# MySensors_AirQuality_Board_2017-11-26_i2.net
KiCad netlist of a schematic drawn in EAGLE
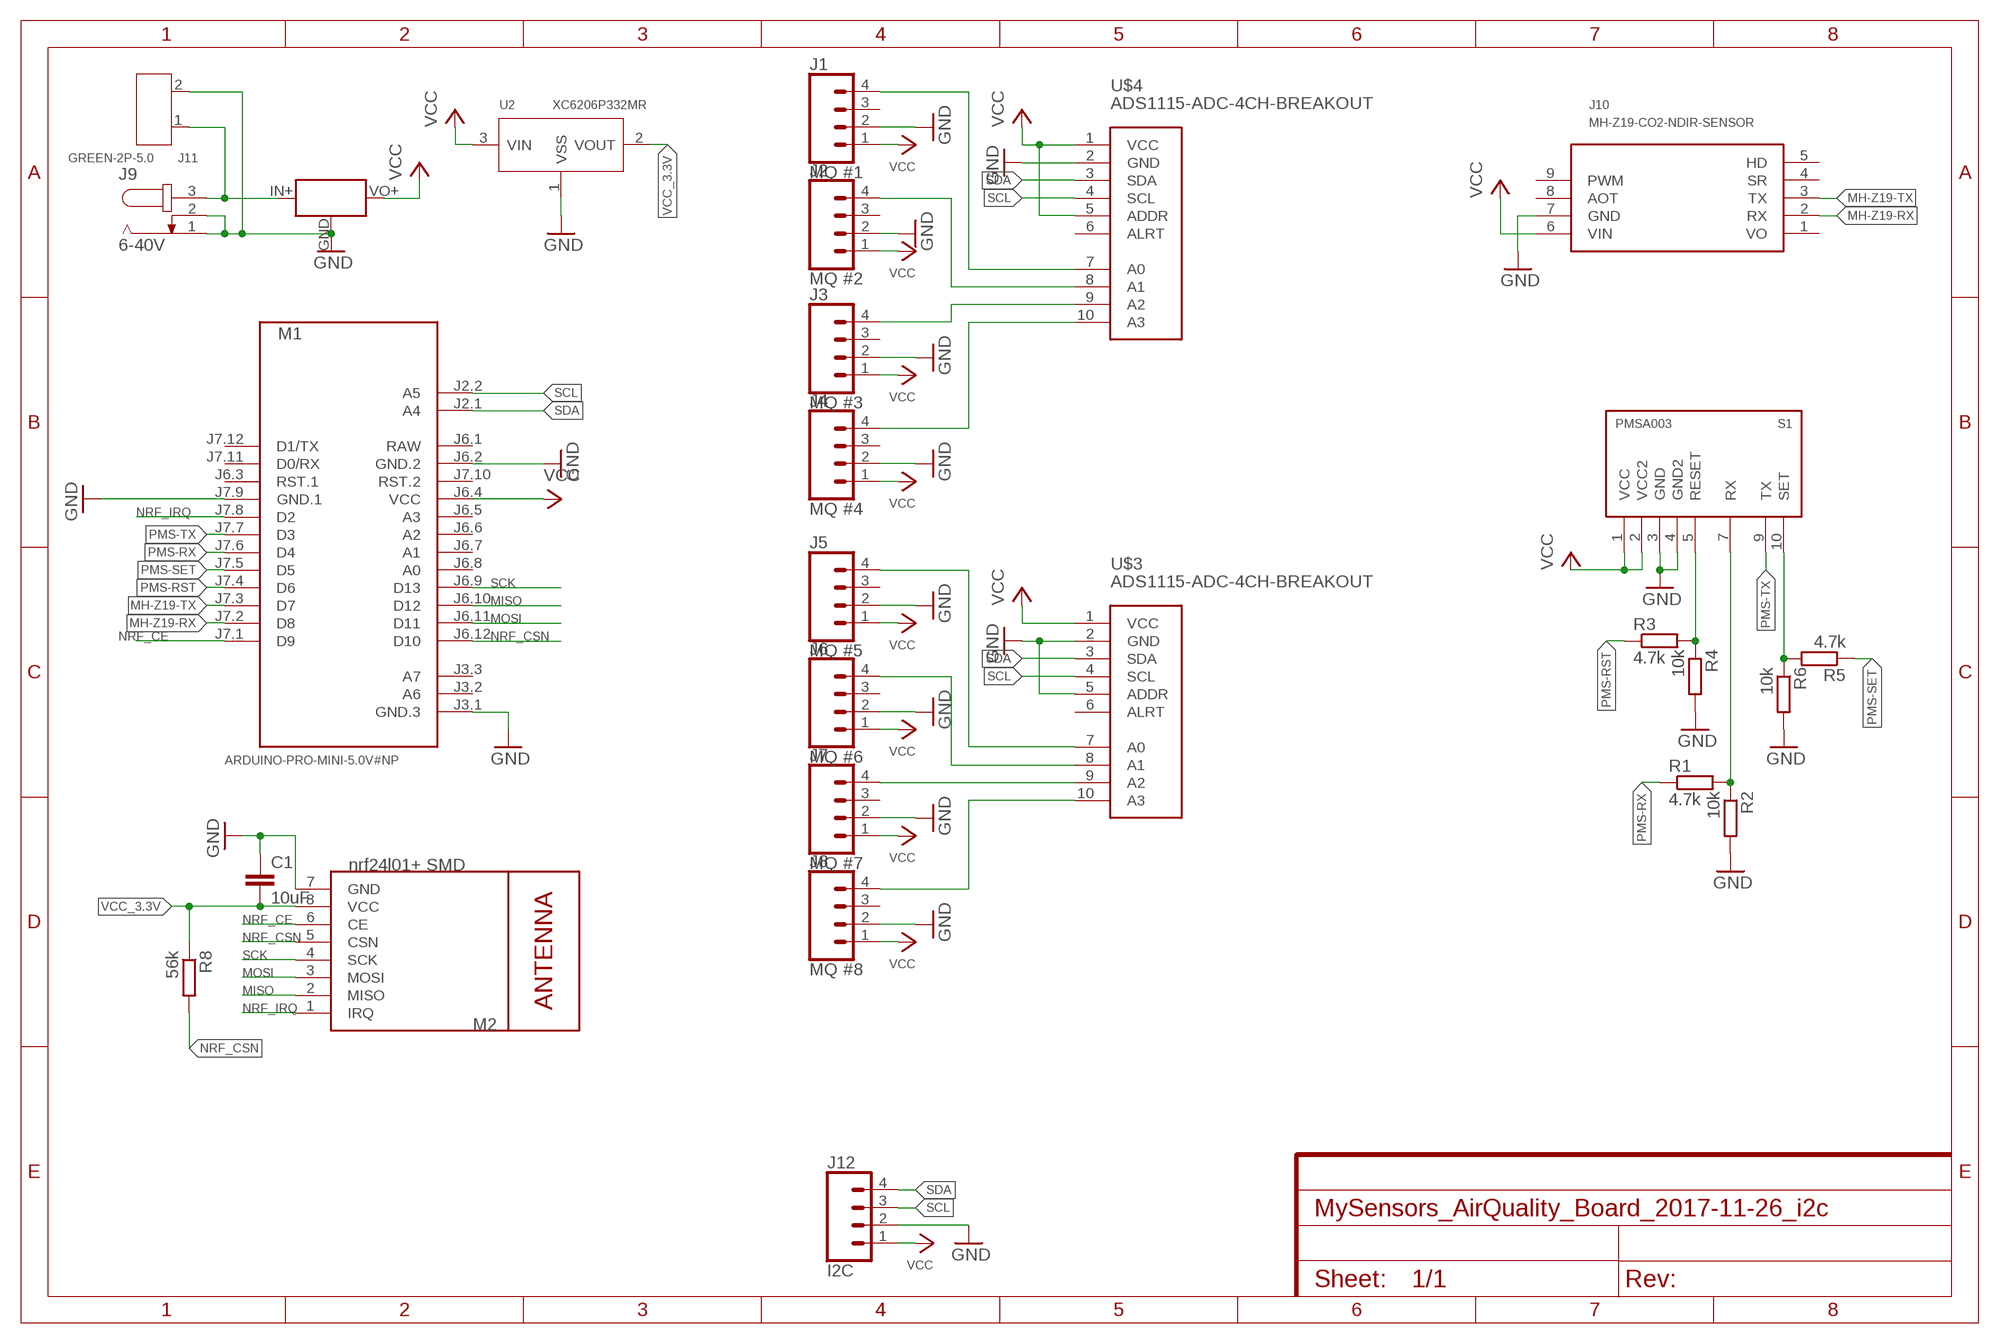
[diagram p0: schematic, sheet 1]

(export (version "E")
  (design (tool "Eeschema 10.0.6"))
  (components
    (comp (ref "C1")
      (value "10uF")
      (footprint "eagle-import:C0805")
      (libsource (lib "eagle-import") (part "C-EUC0805"))
    )
    (comp (ref "J1")
      (value "MQ #1")
      (footprint "eagle-import:1X04")
      (libsource (lib "eagle-import") (part "CONN_04"))
    )
    (comp (ref "J2")
      (value "MQ #2")
      (footprint "eagle-import:1X04")
      (libsource (lib "eagle-import") (part "CONN_04"))
    )
    (comp (ref "J3")
      (value "MQ #3")
      (footprint "eagle-import:1X04")
      (libsource (lib "eagle-import") (part "CONN_04"))
    )
    (comp (ref "J4")
      (value "MQ #4")
      (footprint "eagle-import:1X04")
      (libsource (lib "eagle-import") (part "CONN_04"))
    )
    (comp (ref "J5")
      (value "MQ #5")
      (footprint "eagle-import:1X04")
      (libsource (lib "eagle-import") (part "CONN_04"))
    )
    (comp (ref "J6")
      (value "MQ #6")
      (footprint "eagle-import:1X04")
      (libsource (lib "eagle-import") (part "CONN_04"))
    )
    (comp (ref "J7")
      (value "MQ #7")
      (footprint "eagle-import:1X04")
      (libsource (lib "eagle-import") (part "CONN_04"))
    )
    (comp (ref "J8")
      (value "MQ #8")
      (footprint "eagle-import:1X04")
      (libsource (lib "eagle-import") (part "CONN_04"))
    )
    (comp (ref "J9")
      (value "6-40V")
      (footprint "eagle-import:SPC4078")
      (libsource (lib "eagle-import") (part "JACK-PLUG1"))
    )
    (comp (ref "J10")
      (value "MH-Z19-CO2-NDIR-SENSOR")
      (footprint "eagle-import:MH-Z19")
      (libsource (lib "eagle-import") (part "MH-Z19-CO2-NDIR-SENSOR"))
    )
    (comp (ref "J11")
      (value "GREEN-2P-5.0")
      (footprint "eagle-import:H2-5.0-10.5X8.0MM")
      (libsource (lib "eagle-import") (part "SCREW-TERMINAL-GREEN(2P-5.0)"))
    )
    (comp (ref "J12")
      (value "I2C")
      (footprint "eagle-import:1X04")
      (libsource (lib "eagle-import") (part "CONN_04"))
    )
    (comp (ref "M1")
      (value "ARDUINO-PRO-MINI-5.0V#NP")
      (footprint "eagle-import:ARDUINO-PRO-MINI#NP")
      (libsource (lib "eagle-import") (part "ARDUINO-PRO-MINI-#NP5.0V"))
    )
    (comp (ref "M2")
      (value "nrf24l01+ SMD")
      (footprint "eagle-import:WIRELESS-NRF24L01-SMD")
      (libsource (lib "eagle-import") (part "WIRELESS-NRF24L01SMD"))
    )
    (comp (ref "R1")
      (value "4.7k")
      (footprint "eagle-import:R0805")
      (libsource (lib "eagle-import") (part "resistor_348_R-EU_R0805"))
    )
    (comp (ref "R2")
      (value "10k")
      (footprint "eagle-import:R0805")
      (libsource (lib "eagle-import") (part "resistor_348_R-EU_R0805"))
    )
    (comp (ref "R3")
      (value "4.7k")
      (footprint "eagle-import:R0805")
      (libsource (lib "eagle-import") (part "resistor_348_R-EU_R0805"))
    )
    (comp (ref "R4")
      (value "10k")
      (footprint "eagle-import:R0805")
      (libsource (lib "eagle-import") (part "resistor_348_R-EU_R0805"))
    )
    (comp (ref "R5")
      (value "4.7k")
      (footprint "eagle-import:R0805")
      (libsource (lib "eagle-import") (part "resistor_348_R-EU_R0805"))
    )
    (comp (ref "R6")
      (value "10k")
      (footprint "eagle-import:R0805")
      (libsource (lib "eagle-import") (part "resistor_348_R-EU_R0805"))
    )
    (comp (ref "R8")
      (value "56k")
      (footprint "eagle-import:R0805")
      (libsource (lib "eagle-import") (part "R-EU_R0805"))
    )
    (comp (ref "S1")
      (value "PMSA003")
      (footprint "eagle-import:PMSA003")
      (libsource (lib "eagle-import") (part "PMSA003"))
    )
    (comp (ref "U$2")
      (value "MINI_BUCK_CONVERTER")
      (footprint "eagle-import:MINI_BUCK_CONVERTER")
      (libsource (lib "eagle-import") (part "MINI_BUCK_CONVERTER"))
    )
    (comp (ref "U$3")
      (value "ADS1115-ADC-4CH-BREAKOUT")
      (footprint "eagle-import:ADS1115-ADC-4CH-BREAKOUT")
      (libsource (lib "eagle-import") (part "ADS1115-ADC-4CH-BREAKOUT"))
    )
    (comp (ref "U$4")
      (value "ADS1115-ADC-4CH-BREAKOUT")
      (footprint "eagle-import:ADS1115-ADC-4CH-BREAKOUT")
      (libsource (lib "eagle-import") (part "ADS1115-ADC-4CH-BREAKOUT"))
    )
    (comp (ref "U2")
      (value "XC6206P332MR")
      (footprint "eagle-import:SOT-23")
      (fields (field (name "MPN") "XC6206P332MR-G"))
      (libsource (lib "eagle-import") (part "PMIC-LDO-XC6206P332MR-G(SOT23)"))
    )
  )
  (nets
    (net (code "1") (name "/MISO") (class "Default")
      (node (ref "M1") (pin "J6.10") (pinfunction "D12_J6.10") (pintype "bidirectional"))
      (node (ref "M2") (pin "2") (pinfunction "MISO_2") (pintype "bidirectional"))
    )
    (net (code "2") (name "/MOSI") (class "Default")
      (node (ref "M1") (pin "J6.11") (pinfunction "D11_J6.11") (pintype "bidirectional"))
      (node (ref "M2") (pin "3") (pinfunction "MOSI_3") (pintype "bidirectional"))
    )
    (net (code "3") (name "/NRF_CE") (class "Default")
      (node (ref "M1") (pin "J7.1") (pinfunction "D9_J7.1") (pintype "bidirectional"))
      (node (ref "M2") (pin "6") (pinfunction "CE_6") (pintype "bidirectional"))
    )
    (net (code "4") (name "/NRF_IRQ") (class "Default")
      (node (ref "M1") (pin "J7.8") (pinfunction "D2_J7.8") (pintype "bidirectional"))
      (node (ref "M2") (pin "1") (pinfunction "IRQ_1") (pintype "bidirectional"))
    )
    (net (code "5") (name "/RAW") (class "Default")
      (node (ref "M1") (pin "J6.1") (pinfunction "RAW_J6.1") (pintype "power_in"))
    )
    (net (code "6") (name "/SCK") (class "Default")
      (node (ref "M1") (pin "J6.9") (pinfunction "D13_J6.9") (pintype "bidirectional"))
      (node (ref "M2") (pin "4") (pinfunction "SCK_4") (pintype "bidirectional"))
    )
    (net (code "7") (name "/VO") (class "Default")
      (node (ref "J10") (pin "1") (pinfunction "VO_1") (pintype "power_in"))
    )
    (net (code "8") (name "GND") (class "Default")
      (node (ref "C1") (pin "1") (pinfunction "1_1") (pintype "passive"))
      (node (ref "J1") (pin "2") (pinfunction "2_2") (pintype "passive"))
      (node (ref "J10") (pin "7") (pinfunction "GND_7") (pintype "power_in"))
      (node (ref "J11") (pin "2") (pinfunction "2_2") (pintype "bidirectional"))
      (node (ref "J12") (pin "2") (pinfunction "2_2") (pintype "passive"))
      (node (ref "J2") (pin "2") (pinfunction "2_2") (pintype "passive"))
      (node (ref "J3") (pin "2") (pinfunction "2_2") (pintype "passive"))
      (node (ref "J4") (pin "2") (pinfunction "2_2") (pintype "passive"))
      (node (ref "J5") (pin "2") (pinfunction "2_2") (pintype "passive"))
      (node (ref "J6") (pin "2") (pinfunction "2_2") (pintype "passive"))
      (node (ref "J7") (pin "2") (pinfunction "2_2") (pintype "passive"))
      (node (ref "J8") (pin "2") (pinfunction "2_2") (pintype "passive"))
      (node (ref "J9") (pin "1") (pinfunction "1_1") (pintype "passive"))
      (node (ref "J9") (pin "2") (pinfunction "2_2") (pintype "passive"))
      (node (ref "M1") (pin "J3.1") (pinfunction "GND.3_J3.1") (pintype "bidirectional"))
      (node (ref "M1") (pin "J6.2") (pinfunction "GND.2_J6.2") (pintype "power_in"))
      (node (ref "M1") (pin "J7.9") (pinfunction "GND.1_J7.9") (pintype "power_in"))
      (node (ref "M2") (pin "7") (pinfunction "GND_7") (pintype "power_in"))
      (node (ref "R2") (pin "2") (pinfunction "2_2") (pintype "passive"))
      (node (ref "R4") (pin "2") (pinfunction "2_2") (pintype "passive"))
      (node (ref "R6") (pin "2") (pinfunction "2_2") (pintype "passive"))
      (node (ref "S1") (pin "3") (pinfunction "GND_3") (pintype "bidirectional"))
      (node (ref "S1") (pin "4") (pinfunction "GND2_4") (pintype "bidirectional"))
      (node (ref "U$2") (pin "GND") (pinfunction "GND_GND") (pintype "bidirectional"))
      (node (ref "U$3") (pin "2") (pinfunction "GND_2") (pintype "power_in"))
      (node (ref "U$3") (pin "5") (pinfunction "ADDR_5") (pintype "bidirectional"))
      (node (ref "U$4") (pin "2") (pinfunction "GND_2") (pintype "power_in"))
      (node (ref "U2") (pin "1") (pinfunction "VSS_1") (pintype "power_in"))
    )
    (net (code "9") (name "MH-Z19-RX") (class "Default")
      (node (ref "J10") (pin "2") (pinfunction "RX_2") (pintype "input"))
      (node (ref "M1") (pin "J7.2") (pinfunction "D8_J7.2") (pintype "bidirectional"))
    )
    (net (code "10") (name "MH-Z19-TX") (class "Default")
      (node (ref "J10") (pin "3") (pinfunction "TX_3") (pintype "output"))
      (node (ref "M1") (pin "J7.3") (pinfunction "D7_J7.3") (pintype "bidirectional"))
    )
    (net (code "11") (name "NRF_CSN") (class "Default")
      (node (ref "M1") (pin "J6.12") (pinfunction "D10_J6.12") (pintype "bidirectional"))
      (node (ref "M2") (pin "5") (pinfunction "CSN_5") (pintype "bidirectional"))
      (node (ref "R8") (pin "2") (pinfunction "2_2") (pintype "passive"))
    )
    (net (code "12") (name "Net-(S1-RESET)") (class "Default")
      (node (ref "R3") (pin "2") (pinfunction "2_2") (pintype "passive"))
      (node (ref "R4") (pin "1") (pinfunction "1_1") (pintype "passive"))
      (node (ref "S1") (pin "5") (pinfunction "RESET_5") (pintype "bidirectional"))
    )
    (net (code "13") (name "Net-(S1-RX)") (class "Default")
      (node (ref "R1") (pin "2") (pinfunction "2_2") (pintype "passive"))
      (node (ref "R2") (pin "1") (pinfunction "1_1") (pintype "passive"))
      (node (ref "S1") (pin "7") (pinfunction "RX_7") (pintype "bidirectional"))
    )
    (net (code "14") (name "Net-(S1-SET)") (class "Default")
      (node (ref "R5") (pin "2") (pinfunction "2_2") (pintype "passive"))
      (node (ref "R6") (pin "1") (pinfunction "1_1") (pintype "passive"))
      (node (ref "S1") (pin "10") (pinfunction "SET_10") (pintype "bidirectional"))
    )
    (net (code "15") (name "Net-(U$2-VIN)") (class "Default")
      (node (ref "J11") (pin "1") (pinfunction "1_1") (pintype "bidirectional"))
      (node (ref "J9") (pin "3") (pinfunction "3_3") (pintype "passive"))
      (node (ref "U$2") (pin "IN+") (pinfunction "VIN_IN+") (pintype "input"))
    )
    (net (code "16") (name "Net-(U$3-A0)") (class "Default")
      (node (ref "J5") (pin "4") (pinfunction "4_4") (pintype "passive"))
      (node (ref "U$3") (pin "7") (pinfunction "A0_7") (pintype "input"))
    )
    (net (code "17") (name "Net-(U$3-A1)") (class "Default")
      (node (ref "J6") (pin "4") (pinfunction "4_4") (pintype "passive"))
      (node (ref "U$3") (pin "8") (pinfunction "A1_8") (pintype "input"))
    )
    (net (code "18") (name "Net-(U$3-A2)") (class "Default")
      (node (ref "J7") (pin "4") (pinfunction "4_4") (pintype "passive"))
      (node (ref "U$3") (pin "9") (pinfunction "A2_9") (pintype "input"))
    )
    (net (code "19") (name "Net-(U$3-A3)") (class "Default")
      (node (ref "J8") (pin "4") (pinfunction "4_4") (pintype "passive"))
      (node (ref "U$3") (pin "10") (pinfunction "A3_10") (pintype "input"))
    )
    (net (code "20") (name "Net-(U$4-A0)") (class "Default")
      (node (ref "J1") (pin "4") (pinfunction "4_4") (pintype "passive"))
      (node (ref "U$4") (pin "7") (pinfunction "A0_7") (pintype "input"))
    )
    (net (code "21") (name "Net-(U$4-A1)") (class "Default")
      (node (ref "J2") (pin "4") (pinfunction "4_4") (pintype "passive"))
      (node (ref "U$4") (pin "8") (pinfunction "A1_8") (pintype "input"))
    )
    (net (code "22") (name "Net-(U$4-A2)") (class "Default")
      (node (ref "J3") (pin "4") (pinfunction "4_4") (pintype "passive"))
      (node (ref "U$4") (pin "9") (pinfunction "A2_9") (pintype "input"))
    )
    (net (code "23") (name "Net-(U$4-A3)") (class "Default")
      (node (ref "J4") (pin "4") (pinfunction "4_4") (pintype "passive"))
      (node (ref "U$4") (pin "10") (pinfunction "A3_10") (pintype "input"))
    )
    (net (code "24") (name "PMS-RST") (class "Default")
      (node (ref "M1") (pin "J7.4") (pinfunction "D6_J7.4") (pintype "bidirectional"))
      (node (ref "R3") (pin "1") (pinfunction "1_1") (pintype "passive"))
    )
    (net (code "25") (name "PMS-RX") (class "Default")
      (node (ref "M1") (pin "J7.6") (pinfunction "D4_J7.6") (pintype "bidirectional"))
      (node (ref "R1") (pin "1") (pinfunction "1_1") (pintype "passive"))
    )
    (net (code "26") (name "PMS-SET") (class "Default")
      (node (ref "M1") (pin "J7.5") (pinfunction "D5_J7.5") (pintype "bidirectional"))
      (node (ref "R5") (pin "1") (pinfunction "1_1") (pintype "passive"))
    )
    (net (code "27") (name "PMS-TX") (class "Default")
      (node (ref "M1") (pin "J7.7") (pinfunction "D3_J7.7") (pintype "bidirectional"))
      (node (ref "S1") (pin "9") (pinfunction "TX_9") (pintype "bidirectional"))
    )
    (net (code "28") (name "SCL") (class "Default")
      (node (ref "J12") (pin "3") (pinfunction "3_3") (pintype "passive"))
      (node (ref "M1") (pin "J2.2") (pinfunction "A5_J2.2") (pintype "bidirectional"))
      (node (ref "U$3") (pin "4") (pinfunction "SCL_4") (pintype "bidirectional"))
      (node (ref "U$4") (pin "4") (pinfunction "SCL_4") (pintype "bidirectional"))
    )
    (net (code "29") (name "SDA") (class "Default")
      (node (ref "J12") (pin "4") (pinfunction "4_4") (pintype "passive"))
      (node (ref "M1") (pin "J2.1") (pinfunction "A4_J2.1") (pintype "bidirectional"))
      (node (ref "U$3") (pin "3") (pinfunction "SDA_3") (pintype "bidirectional"))
      (node (ref "U$4") (pin "3") (pinfunction "SDA_3") (pintype "bidirectional"))
    )
    (net (code "30") (name "VCC") (class "Default")
      (node (ref "J1") (pin "1") (pinfunction "1_1") (pintype "passive"))
      (node (ref "J10") (pin "6") (pinfunction "VIN_6") (pintype "power_in"))
      (node (ref "J12") (pin "1") (pinfunction "1_1") (pintype "passive"))
      (node (ref "J2") (pin "1") (pinfunction "1_1") (pintype "passive"))
      (node (ref "J3") (pin "1") (pinfunction "1_1") (pintype "passive"))
      (node (ref "J4") (pin "1") (pinfunction "1_1") (pintype "passive"))
      (node (ref "J5") (pin "1") (pinfunction "1_1") (pintype "passive"))
      (node (ref "J6") (pin "1") (pinfunction "1_1") (pintype "passive"))
      (node (ref "J7") (pin "1") (pinfunction "1_1") (pintype "passive"))
      (node (ref "J8") (pin "1") (pinfunction "1_1") (pintype "passive"))
      (node (ref "M1") (pin "J6.4") (pinfunction "VCC_J6.4") (pintype "power_in"))
      (node (ref "S1") (pin "1") (pinfunction "VCC_1") (pintype "bidirectional"))
      (node (ref "S1") (pin "2") (pinfunction "VCC2_2") (pintype "bidirectional"))
      (node (ref "U$2") (pin "VO+") (pinfunction "VOUT_VO+") (pintype "power_in"))
      (node (ref "U$3") (pin "1") (pinfunction "VCC_1") (pintype "power_in"))
      (node (ref "U$4") (pin "1") (pinfunction "VCC_1") (pintype "power_in"))
      (node (ref "U$4") (pin "5") (pinfunction "ADDR_5") (pintype "bidirectional"))
      (node (ref "U2") (pin "3") (pinfunction "VIN_3") (pintype "input"))
    )
    (net (code "31") (name "VCC_3.3V") (class "Default")
      (node (ref "C1") (pin "2") (pinfunction "2_2") (pintype "passive"))
      (node (ref "M2") (pin "8") (pinfunction "VCC_8") (pintype "power_in"))
      (node (ref "R8") (pin "1") (pinfunction "1_1") (pintype "passive"))
      (node (ref "U2") (pin "2") (pinfunction "VOUT_2") (pintype "output"))
    )
    (net (code "32") (name "unconnected-(J1-Pad3)") (class "Default")
      (node (ref "J1") (pin "3") (pinfunction "3_3") (pintype "passive"))
    )
    (net (code "33") (name "unconnected-(J2-Pad3)") (class "Default")
      (node (ref "J2") (pin "3") (pinfunction "3_3") (pintype "passive"))
    )
    (net (code "34") (name "unconnected-(J3-Pad3)") (class "Default")
      (node (ref "J3") (pin "3") (pinfunction "3_3") (pintype "passive"))
    )
    (net (code "35") (name "unconnected-(J4-Pad3)") (class "Default")
      (node (ref "J4") (pin "3") (pinfunction "3_3") (pintype "passive"))
    )
    (net (code "36") (name "unconnected-(J5-Pad3)") (class "Default")
      (node (ref "J5") (pin "3") (pinfunction "3_3") (pintype "passive"))
    )
    (net (code "37") (name "unconnected-(J6-Pad3)") (class "Default")
      (node (ref "J6") (pin "3") (pinfunction "3_3") (pintype "passive"))
    )
    (net (code "38") (name "unconnected-(J7-Pad3)") (class "Default")
      (node (ref "J7") (pin "3") (pinfunction "3_3") (pintype "passive"))
    )
    (net (code "39") (name "unconnected-(J8-Pad3)") (class "Default")
      (node (ref "J8") (pin "3") (pinfunction "3_3") (pintype "passive"))
    )
    (net (code "40") (name "unconnected-(J10-AOT-Pad8)") (class "Default")
      (node (ref "J10") (pin "8") (pinfunction "AOT_8") (pintype "no_connect"))
    )
    (net (code "41") (name "unconnected-(J10-HD-Pad5)") (class "Default")
      (node (ref "J10") (pin "5") (pinfunction "HD_5") (pintype "input"))
    )
    (net (code "42") (name "unconnected-(J10-PWM-Pad9)") (class "Default")
      (node (ref "J10") (pin "9") (pinfunction "PWM_9") (pintype "output"))
    )
    (net (code "43") (name "unconnected-(J10-SR-Pad4)") (class "Default")
      (node (ref "J10") (pin "4") (pinfunction "SR_4") (pintype "no_connect"))
    )
    (net (code "44") (name "unconnected-(M1-A0-PadJ6.8)") (class "Default")
      (node (ref "M1") (pin "J6.8") (pinfunction "A0_J6.8") (pintype "bidirectional"))
    )
    (net (code "45") (name "unconnected-(M1-A1-PadJ6.7)") (class "Default")
      (node (ref "M1") (pin "J6.7") (pinfunction "A1_J6.7") (pintype "bidirectional"))
    )
    (net (code "46") (name "unconnected-(M1-A2-PadJ6.6)") (class "Default")
      (node (ref "M1") (pin "J6.6") (pinfunction "A2_J6.6") (pintype "bidirectional"))
    )
    (net (code "47") (name "unconnected-(M1-A3-PadJ6.5)") (class "Default")
      (node (ref "M1") (pin "J6.5") (pinfunction "A3_J6.5") (pintype "bidirectional"))
    )
    (net (code "48") (name "unconnected-(M1-A6-PadJ3.2)") (class "Default")
      (node (ref "M1") (pin "J3.2") (pinfunction "A6_J3.2") (pintype "bidirectional"))
    )
    (net (code "49") (name "unconnected-(M1-A7-PadJ3.3)") (class "Default")
      (node (ref "M1") (pin "J3.3") (pinfunction "A7_J3.3") (pintype "bidirectional"))
    )
    (net (code "50") (name "unconnected-(M1-D0{slash}RX-PadJ7.11)") (class "Default")
      (node (ref "M1") (pin "J7.11") (pinfunction "D0/RX_J7.11") (pintype "bidirectional"))
    )
    (net (code "51") (name "unconnected-(M1-D1{slash}TX-PadJ7.12)") (class "Default")
      (node (ref "M1") (pin "J7.12") (pinfunction "D1/TX_J7.12") (pintype "bidirectional"))
    )
    (net (code "52") (name "unconnected-(M1-RST.1-PadJ6.3)") (class "Default")
      (node (ref "M1") (pin "J6.3") (pinfunction "RST.1_J6.3") (pintype "bidirectional"))
    )
    (net (code "53") (name "unconnected-(M1-RST.2-PadJ7.10)") (class "Default")
      (node (ref "M1") (pin "J7.10") (pinfunction "RST.2_J7.10") (pintype "bidirectional"))
    )
    (net (code "54") (name "unconnected-(U$3-ALRT-Pad6)") (class "Default")
      (node (ref "U$3") (pin "6") (pinfunction "ALRT_6") (pintype "bidirectional"))
    )
    (net (code "55") (name "unconnected-(U$4-ALRT-Pad6)") (class "Default")
      (node (ref "U$4") (pin "6") (pinfunction "ALRT_6") (pintype "bidirectional"))
    )
  )
)
